# Test_PCB_Video_1.net
KiCad netlist of a schematic drawn in EasyEDA Pro
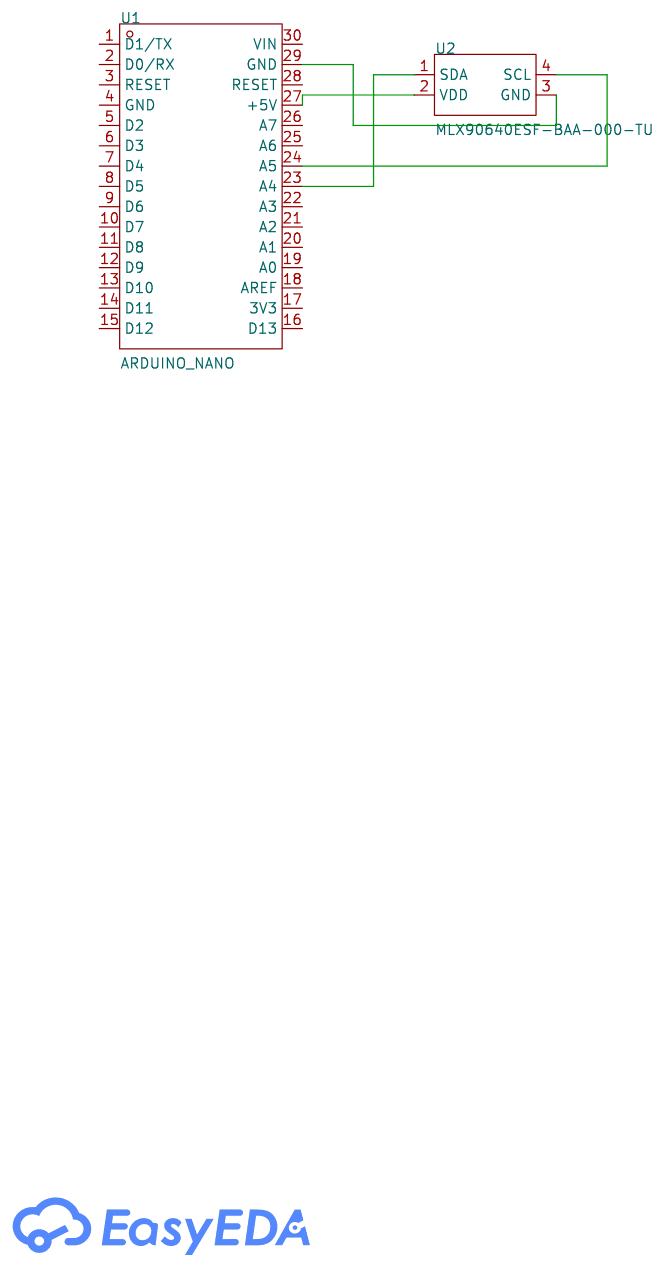
[diagram p0: schematic sheet]

(export (version "E")
  (design (tool "Eeschema 10.0.6"))
  (components
    (comp (ref "U1")
      (value "ARDUINO_NANO")
      (footprint "easyedapro:COMM-TH_ARDUINO_NANO")
      (libsource (lib "easyedapro") (part "ARDUINO_NANO"))
    )
    (comp (ref "U2")
      (value "MLX90640ESF-BAA-000-TU")
      (footprint "easyedapro:TO-39_4P-BD9.3_MLX90640ESF-BAA-000-TU_H5.7")
      (fields (field (name "Manufacturer") "Melexis(比利时迈来芯)"))
      (libsource (lib "easyedapro") (part "MLX90640ESF-BAA-000-TU_C17380659"))
    )
  )
  (nets
    (net (code "1") (name "Net-(U1-+5V)") (class "Default")
      (node (ref "U1") (pin "27") (pinfunction "+5V_27") (pintype "unspecified"))
      (node (ref "U2") (pin "2") (pinfunction "VDD_2") (pintype "unspecified"))
    )
    (net (code "2") (name "Net-(U1-A4)") (class "Default")
      (node (ref "U1") (pin "23") (pinfunction "A4_23") (pintype "unspecified"))
      (node (ref "U2") (pin "1") (pinfunction "SDA_1") (pintype "unspecified"))
    )
    (net (code "3") (name "Net-(U1-A5)") (class "Default")
      (node (ref "U1") (pin "24") (pinfunction "A5_24") (pintype "unspecified"))
      (node (ref "U2") (pin "4") (pinfunction "SCL_4") (pintype "unspecified"))
    )
    (net (code "4") (name "Net-(U2-GND)") (class "Default")
      (node (ref "U1") (pin "29") (pinfunction "GND_29") (pintype "unspecified"))
      (node (ref "U2") (pin "3") (pinfunction "GND_3") (pintype "unspecified"))
    )
    (net (code "5") (name "unconnected-(U1-3V3-Pad17)") (class "Default")
      (node (ref "U1") (pin "17") (pinfunction "3V3_17") (pintype "unspecified"))
    )
    (net (code "6") (name "unconnected-(U1-A0-Pad19)") (class "Default")
      (node (ref "U1") (pin "19") (pinfunction "A0_19") (pintype "unspecified"))
    )
    (net (code "7") (name "unconnected-(U1-A1-Pad20)") (class "Default")
      (node (ref "U1") (pin "20") (pinfunction "A1_20") (pintype "unspecified"))
    )
    (net (code "8") (name "unconnected-(U1-A2-Pad21)") (class "Default")
      (node (ref "U1") (pin "21") (pinfunction "A2_21") (pintype "unspecified"))
    )
    (net (code "9") (name "unconnected-(U1-A3-Pad22)") (class "Default")
      (node (ref "U1") (pin "22") (pinfunction "A3_22") (pintype "unspecified"))
    )
    (net (code "10") (name "unconnected-(U1-A6-Pad25)") (class "Default")
      (node (ref "U1") (pin "25") (pinfunction "A6_25") (pintype "unspecified"))
    )
    (net (code "11") (name "unconnected-(U1-A7-Pad26)") (class "Default")
      (node (ref "U1") (pin "26") (pinfunction "A7_26") (pintype "unspecified"))
    )
    (net (code "12") (name "unconnected-(U1-AREF-Pad18)") (class "Default")
      (node (ref "U1") (pin "18") (pinfunction "AREF_18") (pintype "unspecified"))
    )
    (net (code "13") (name "unconnected-(U1-D0{slash}RX-Pad2)") (class "Default")
      (node (ref "U1") (pin "2") (pinfunction "D0/RX_2") (pintype "unspecified"))
    )
    (net (code "14") (name "unconnected-(U1-D1{slash}TX-Pad1)") (class "Default")
      (node (ref "U1") (pin "1") (pinfunction "D1/TX_1") (pintype "unspecified"))
    )
    (net (code "15") (name "unconnected-(U1-D2-Pad5)") (class "Default")
      (node (ref "U1") (pin "5") (pinfunction "D2_5") (pintype "unspecified"))
    )
    (net (code "16") (name "unconnected-(U1-D3-Pad6)") (class "Default")
      (node (ref "U1") (pin "6") (pinfunction "D3_6") (pintype "unspecified"))
    )
    (net (code "17") (name "unconnected-(U1-D4-Pad7)") (class "Default")
      (node (ref "U1") (pin "7") (pinfunction "D4_7") (pintype "unspecified"))
    )
    (net (code "18") (name "unconnected-(U1-D5-Pad8)") (class "Default")
      (node (ref "U1") (pin "8") (pinfunction "D5_8") (pintype "unspecified"))
    )
    (net (code "19") (name "unconnected-(U1-D6-Pad9)") (class "Default")
      (node (ref "U1") (pin "9") (pinfunction "D6_9") (pintype "unspecified"))
    )
    (net (code "20") (name "unconnected-(U1-D7-Pad10)") (class "Default")
      (node (ref "U1") (pin "10") (pinfunction "D7_10") (pintype "unspecified"))
    )
    (net (code "21") (name "unconnected-(U1-D8-Pad11)") (class "Default")
      (node (ref "U1") (pin "11") (pinfunction "D8_11") (pintype "unspecified"))
    )
    (net (code "22") (name "unconnected-(U1-D9-Pad12)") (class "Default")
      (node (ref "U1") (pin "12") (pinfunction "D9_12") (pintype "unspecified"))
    )
    (net (code "23") (name "unconnected-(U1-D10-Pad13)") (class "Default")
      (node (ref "U1") (pin "13") (pinfunction "D10_13") (pintype "unspecified"))
    )
    (net (code "24") (name "unconnected-(U1-D11-Pad14)") (class "Default")
      (node (ref "U1") (pin "14") (pinfunction "D11_14") (pintype "unspecified"))
    )
    (net (code "25") (name "unconnected-(U1-D12-Pad15)") (class "Default")
      (node (ref "U1") (pin "15") (pinfunction "D12_15") (pintype "unspecified"))
    )
    (net (code "26") (name "unconnected-(U1-D13-Pad16)") (class "Default")
      (node (ref "U1") (pin "16") (pinfunction "D13_16") (pintype "unspecified"))
    )
    (net (code "27") (name "unconnected-(U1-GND-Pad4)") (class "Default")
      (node (ref "U1") (pin "4") (pinfunction "GND_4") (pintype "unspecified"))
    )
    (net (code "28") (name "unconnected-(U1-RESET-Pad3)") (class "Default")
      (node (ref "U1") (pin "3") (pinfunction "RESET_3") (pintype "unspecified"))
    )
    (net (code "29") (name "unconnected-(U1-RESET-Pad28)") (class "Default")
      (node (ref "U1") (pin "28") (pinfunction "RESET_28") (pintype "unspecified"))
    )
    (net (code "30") (name "unconnected-(U1-VIN-Pad30)") (class "Default")
      (node (ref "U1") (pin "30") (pinfunction "VIN_30") (pintype "unspecified"))
    )
  )
)
